# SOM_Analog_USB.net
KiCad netlist of a schematic drawn in Altium Designer
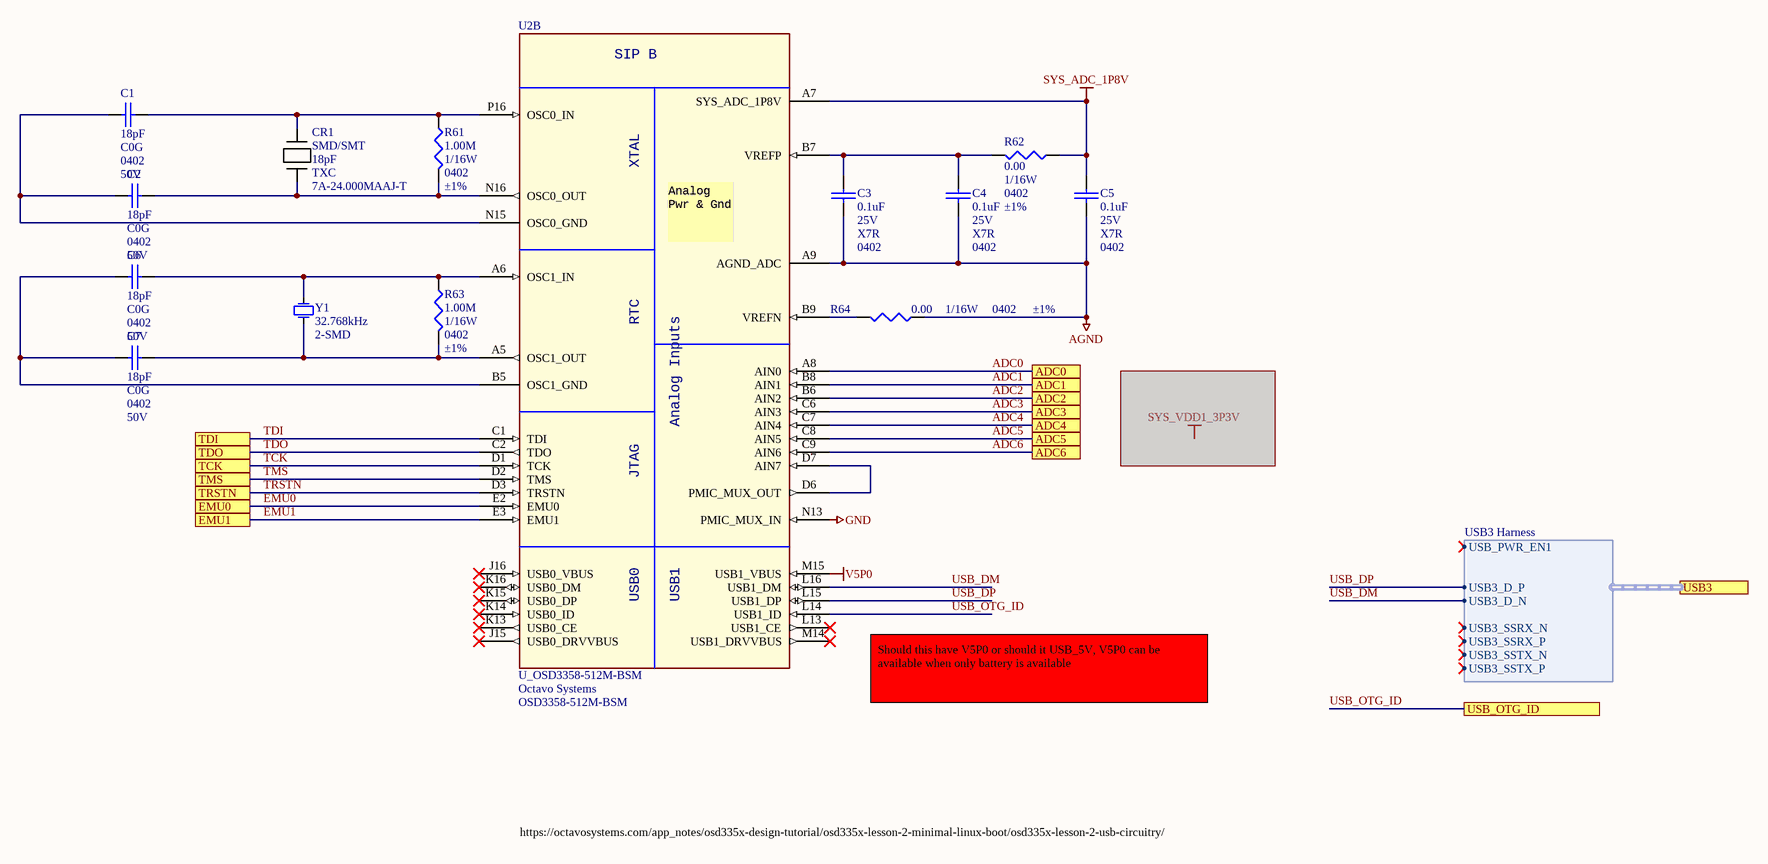
[diagram p0: SOM Analog USB.SchDoc]

(export (version "E")
  (design (tool "Eeschema 10.0.6"))
  (components
    (comp (ref "C1")
      (value "C_0402_18PF_50V")
      (footprint "C_0402")
      (fields
        (field (name "CAPACITANCE") "18pF")
        (field (name "TOLERANCE") "5%")
        (field (name "DIELECTRIC") "C0G")
        (field (name "CASE CODE (IMPERIAL)") "0402")
        (field (name "VOLTAGE RATING") "50V")
      )
      (libsource (lib "Cospan Design") (part "C_0402_18PF_50V"))
    )
    (comp (ref "C2")
      (value "C_0402_18PF_50V")
      (footprint "C_0402")
      (fields
        (field (name "CAPACITANCE") "18pF")
        (field (name "TOLERANCE") "5%")
        (field (name "DIELECTRIC") "C0G")
        (field (name "CASE CODE (IMPERIAL)") "0402")
        (field (name "VOLTAGE RATING") "50V")
      )
      (libsource (lib "Cospan Design") (part "C_0402_18PF_50V"))
    )
    (comp (ref "C3")
      (value "C_0402_0.1UF_25V")
      (footprint "C_0402")
      (description "CAP CER 0.1UF 25V X6S 0402")
      (fields
        (field (name "TOLERANCE") "10%")
        (field (name "CAPACITANCE") "0.1uF")
        (field (name "VOLTAGE - RATED") "25V")
        (field (name "TEMPERATURE COEFFICIENT") "X7R")
        (field (name "PACKAGE / CASE") "0402")
      )
      (libsource (lib "Cospan Design") (part "C_0402_0.1UF_25V"))
    )
    (comp (ref "C4")
      (value "C_0402_0.1UF_25V")
      (footprint "C_0402")
      (description "CAP CER 0.1UF 25V X6S 0402")
      (fields
        (field (name "TOLERANCE") "10%")
        (field (name "CAPACITANCE") "0.1uF")
        (field (name "VOLTAGE - RATED") "25V")
        (field (name "TEMPERATURE COEFFICIENT") "X7R")
        (field (name "PACKAGE / CASE") "0402")
      )
      (libsource (lib "Cospan Design") (part "C_0402_0.1UF_25V"))
    )
    (comp (ref "C5")
      (value "C_0402_0.1UF_25V")
      (footprint "C_0402")
      (description "CAP CER 0.1UF 25V X6S 0402")
      (fields
        (field (name "TOLERANCE") "10%")
        (field (name "CAPACITANCE") "0.1uF")
        (field (name "VOLTAGE - RATED") "25V")
        (field (name "TEMPERATURE COEFFICIENT") "X7R")
        (field (name "PACKAGE / CASE") "0402")
      )
      (libsource (lib "Cospan Design") (part "C_0402_0.1UF_25V"))
    )
    (comp (ref "C6")
      (value "C_0402_18PF_50V")
      (footprint "C_0402")
      (fields
        (field (name "CAPACITANCE") "18pF")
        (field (name "TOLERANCE") "5%")
        (field (name "DIELECTRIC") "C0G")
        (field (name "CASE CODE (IMPERIAL)") "0402")
        (field (name "VOLTAGE RATING") "50V")
      )
      (libsource (lib "Cospan Design") (part "C_0402_18PF_50V"))
    )
    (comp (ref "C7")
      (value "C_0402_18PF_50V")
      (footprint "C_0402")
      (fields
        (field (name "CAPACITANCE") "18pF")
        (field (name "TOLERANCE") "5%")
        (field (name "DIELECTRIC") "C0G")
        (field (name "CASE CODE (IMPERIAL)") "0402")
        (field (name "VOLTAGE RATING") "50V")
      )
      (libsource (lib "Cospan Design") (part "C_0402_18PF_50V"))
    )
    (comp (ref "CR1")
      (value "Y_7A-24.000MAAJ-T")
      (footprint "CRYSTAL_TXC_7A")
      (description "Imported")
      (fields
        (field (name "MANUFACTURER_PART_NUMBER") "7A-24.000MAAJ-T")
        (field (name "TOLERANCE") "30ppm")
        (field (name "CASE/PACKAGE") "SMD/SMT")
        (field (name "LOAD CAPACITANCE") "18pF")
        (field (name "MANUFACTURER 1") "TXC")
        (field (name "MANUFACTURER PART NUMBER 1") "7A-24.000MAAJ-T")
      )
      (libsource (lib "Cospan Design") (part "Y_7A-24.000MAAJ-T"))
    )
    (comp (ref "R61")
      (value "1.0M Ohms")
      (footprint "R_0402")
      (description "RES 1.00M OHM 1/16W 1% 0402 SMD")
      (fields
        (field (name "MANUFACTURER") "Vishay/Dale")
        (field (name "MANUFACTURER PART NUMBER") "CRCW04021M00FKED")
        (field (name "RESISTANCE IN OHMS") "1.00M")
        (field (name "POWER (WATTS)") "1/16W")
        (field (name "CASE") "0402")
        (field (name "TOLERANCE") "±1%")
      )
      (libsource (lib "Main Library") (part "R_0402_1.0M"))
    )
    (comp (ref "R62")
      (value "0.0 Ohms")
      (footprint "R_0402")
      (description "RES 0.00 OHM 1/16W 1% 0402 SMD")
      (fields
        (field (name "MANUFACTURER") "Yageo")
        (field (name "MANUFACTURER PART NUMBER") "RC0402JR-070RL")
        (field (name "RESISTANCE IN OHMS") "0.00")
        (field (name "POWER (WATTS)") "1/16W")
        (field (name "CASE") "0402")
        (field (name "TOLERANCE") "±1%")
      )
      (libsource (lib "Cospan Design") (part "R_0402_0.00"))
    )
    (comp (ref "R63")
      (value "1.0M Ohms")
      (footprint "R_0402")
      (description "RES 1.00M OHM 1/16W 1% 0402 SMD")
      (fields
        (field (name "MANUFACTURER") "Vishay/Dale")
        (field (name "MANUFACTURER PART NUMBER") "CRCW04021M00FKED")
        (field (name "RESISTANCE IN OHMS") "1.00M")
        (field (name "POWER (WATTS)") "1/16W")
        (field (name "CASE") "0402")
        (field (name "TOLERANCE") "±1%")
      )
      (libsource (lib "Main Library") (part "R_0402_1.0M"))
    )
    (comp (ref "R64")
      (value "0.0 Ohms")
      (footprint "R_0402")
      (description "RES 0.00 OHM 1/16W 1% 0402 SMD")
      (fields
        (field (name "MANUFACTURER") "Yageo")
        (field (name "MANUFACTURER PART NUMBER") "RC0402JR-070RL")
        (field (name "RESISTANCE IN OHMS") "0.00")
        (field (name "POWER (WATTS)") "1/16W")
        (field (name "CASE") "0402")
        (field (name "TOLERANCE") "±1%")
      )
      (libsource (lib "Cospan Design") (part "R_0402_0.00"))
    )
    (comp (ref "U2")
      (value "U_OSD3358-512M-BSM")
      (footprint "OSD335X-BGA-256")
      (fields
        (field (name "MANUFACTURER 1") "Octavo Systems")
        (field (name "MANUFACTURER PART NUMBER 1") "OSD3358-512M-BSM")
      )
      (libsource (lib "Cospan Design") (part "U_OSD3358-512M-BSM"))
    )
    (comp (ref "Y1")
      (value "32.768kHz (Tuning Fork)")
      (footprint "FC-135_CRYSTAL")
      (description "CRYSTAL 32.7680KHZ 12.5PF SMD")
      (fields
        (field (name "MANUFACTURER") "Epson Toyocom Corporation")
        (field (name "MANUFACTURER PART NUMBER") "FC-135 32.7680KA-A3")
        (field (name "FREQUENCY") "32.768kHz")
        (field (name "PACKAGE / CASE") "2-SMD")
      )
      (libsource (lib "Main Library") (part "Y_SMD_32KHZ"))
    )
  )
  (nets
    (net (code "3") (name "/ADC0") (class "Default")
      (node (ref "U2") (pin "A8") (pinfunction "AIN0_A8") (pintype "input"))
    )
    (net (code "4") (name "/ADC1") (class "Default")
      (node (ref "U2") (pin "B8") (pinfunction "AIN1_B8") (pintype "input"))
    )
    (net (code "5") (name "/ADC2") (class "Default")
      (node (ref "U2") (pin "B6") (pinfunction "AIN2_B6") (pintype "input"))
    )
    (net (code "6") (name "/ADC3") (class "Default")
      (node (ref "U2") (pin "C6") (pinfunction "AIN3_C6") (pintype "input"))
    )
    (net (code "7") (name "/ADC4") (class "Default")
      (node (ref "U2") (pin "C7") (pinfunction "AIN4_C7") (pintype "input"))
    )
    (net (code "8") (name "/ADC5") (class "Default")
      (node (ref "U2") (pin "C8") (pinfunction "AIN5_C8") (pintype "input"))
    )
    (net (code "9") (name "/ADC6") (class "Default")
      (node (ref "U2") (pin "C9") (pinfunction "AIN6_C9") (pintype "input"))
    )
    (net (code "10") (name "/EMU0") (class "Default")
      (node (ref "U2") (pin "E2") (pinfunction "EMU0_E2") (pintype "input"))
    )
    (net (code "11") (name "/EMU1") (class "Default")
      (node (ref "U2") (pin "E3") (pinfunction "EMU1_E3") (pintype "input"))
    )
    (net (code "12") (name "/TCK") (class "Default")
      (node (ref "U2") (pin "D1") (pinfunction "TCK_D1") (pintype "input"))
    )
    (net (code "13") (name "/TDI") (class "Default")
      (node (ref "U2") (pin "C1") (pinfunction "TDI_C1") (pintype "input"))
    )
    (net (code "14") (name "/TDO") (class "Default")
      (node (ref "U2") (pin "C2") (pinfunction "TDO_C2") (pintype "output"))
    )
    (net (code "15") (name "/TMS") (class "Default")
      (node (ref "U2") (pin "D2") (pinfunction "TMS_D2") (pintype "input"))
    )
    (net (code "16") (name "/TRSTN") (class "Default")
      (node (ref "U2") (pin "D3") (pinfunction "TRSTN_D3") (pintype "input"))
    )
    (net (code "17") (name "/USB_DM") (class "Default")
      (node (ref "U2") (pin "L16") (pinfunction "USB1_DM_L16") (pintype "bidirectional"))
    )
    (net (code "18") (name "/USB_DP") (class "Default")
      (node (ref "U2") (pin "L15") (pinfunction "USB1_DP_L15") (pintype "bidirectional"))
    )
    (net (code "19") (name "/USB_OTG_ID") (class "Default")
      (node (ref "U2") (pin "L14") (pinfunction "USB1_ID_L14") (pintype "input"))
    )
    (net (code "21") (name "AGND") (class "Default")
      (node (ref "C3") (pin "1") (pinfunction "1_1") (pintype "passive"))
      (node (ref "C4") (pin "1") (pinfunction "1_1") (pintype "passive"))
      (node (ref "C5") (pin "1") (pinfunction "1_1") (pintype "passive"))
      (node (ref "R64") (pin "2") (pinfunction "2_2") (pintype "passive"))
      (node (ref "U2") (pin "A9") (pinfunction "AGND_ADC_A9") (pintype "power_in"))
    )
    (net (code "22") (name "GND") (class "Default")
      (node (ref "U2") (pin "N13") (pinfunction "PMIC_MUX_IN_N13") (pintype "input"))
    )
    (net (code "23") (name "Net-(U2B-AIN7)") (class "Default")
      (node (ref "U2") (pin "D6") (pinfunction "PMIC_MUX_OUT_D6") (pintype "output"))
      (node (ref "U2") (pin "D7") (pinfunction "AIN7_D7") (pintype "input"))
    )
    (net (code "24") (name "Net-(U2B-OSC0_GND)") (class "Default")
      (node (ref "C1") (pin "1") (pinfunction "1_1") (pintype "passive"))
      (node (ref "C2") (pin "1") (pinfunction "1_1") (pintype "passive"))
      (node (ref "U2") (pin "N15") (pinfunction "OSC0_GND_N15") (pintype "power_in"))
    )
    (net (code "25") (name "Net-(U2B-OSC0_IN)") (class "Default")
      (node (ref "C1") (pin "2") (pinfunction "2_2") (pintype "passive"))
      (node (ref "CR1") (pin "2") (pinfunction "2_2") (pintype "passive"))
      (node (ref "R61") (pin "2") (pinfunction "2_2") (pintype "passive"))
      (node (ref "U2") (pin "P16") (pinfunction "OSC0_IN_P16") (pintype "input"))
    )
    (net (code "26") (name "Net-(U2B-OSC0_OUT)") (class "Default")
      (node (ref "C2") (pin "2") (pinfunction "2_2") (pintype "passive"))
      (node (ref "CR1") (pin "1") (pinfunction "1_1") (pintype "passive"))
      (node (ref "R61") (pin "1") (pinfunction "1_1") (pintype "passive"))
      (node (ref "U2") (pin "N16") (pinfunction "OSC0_OUT_N16") (pintype "output"))
    )
    (net (code "27") (name "Net-(U2B-OSC1_GND)") (class "Default")
      (node (ref "C6") (pin "1") (pinfunction "1_1") (pintype "passive"))
      (node (ref "C7") (pin "1") (pinfunction "1_1") (pintype "passive"))
      (node (ref "U2") (pin "B5") (pinfunction "OSC1_GND_B5") (pintype "power_in"))
    )
    (net (code "28") (name "Net-(U2B-OSC1_IN)") (class "Default")
      (node (ref "C6") (pin "2") (pinfunction "2_2") (pintype "passive"))
      (node (ref "R63") (pin "2") (pinfunction "2_2") (pintype "passive"))
      (node (ref "U2") (pin "A6") (pinfunction "OSC1_IN_A6") (pintype "input"))
      (node (ref "Y1") (pin "1") (pinfunction "1_1") (pintype "passive"))
    )
    (net (code "29") (name "Net-(U2B-OSC1_OUT)") (class "Default")
      (node (ref "C7") (pin "2") (pinfunction "2_2") (pintype "passive"))
      (node (ref "R63") (pin "1") (pinfunction "1_1") (pintype "passive"))
      (node (ref "U2") (pin "A5") (pinfunction "OSC1_OUT_A5") (pintype "output"))
      (node (ref "Y1") (pin "2") (pinfunction "2_2") (pintype "passive"))
    )
    (net (code "30") (name "Net-(U2B-VREFN)") (class "Default")
      (node (ref "R64") (pin "1") (pinfunction "1_1") (pintype "passive"))
      (node (ref "U2") (pin "B9") (pinfunction "VREFN_B9") (pintype "input"))
    )
    (net (code "31") (name "Net-(U2B-VREFP)") (class "Default")
      (node (ref "C3") (pin "2") (pinfunction "2_2") (pintype "passive"))
      (node (ref "C4") (pin "2") (pinfunction "2_2") (pintype "passive"))
      (node (ref "R62") (pin "1") (pinfunction "1_1") (pintype "passive"))
      (node (ref "U2") (pin "B7") (pinfunction "VREFP_B7") (pintype "input"))
    )
    (net (code "32") (name "SYS_ADC_1P8V") (class "Default")
      (node (ref "C5") (pin "2") (pinfunction "2_2") (pintype "passive"))
      (node (ref "R62") (pin "2") (pinfunction "2_2") (pintype "passive"))
      (node (ref "U2") (pin "A7") (pinfunction "SYS_ADC_1P8V_A7") (pintype "power_in"))
    )
    (net (code "34") (name "V5P0") (class "Default")
      (node (ref "U2") (pin "M15") (pinfunction "USB1_VBUS_M15") (pintype "input"))
    )
    (net (code "35") (name "unconnected-(U2B-USB0_CE-PadK13)") (class "Default")
      (node (ref "U2") (pin "K13") (pinfunction "USB0_CE_K13") (pintype "output+no_connect"))
    )
    (net (code "36") (name "unconnected-(U2B-USB0_DM-PadK16)") (class "Default")
      (node (ref "U2") (pin "K16") (pinfunction "USB0_DM_K16") (pintype "bidirectional+no_connect"))
    )
    (net (code "37") (name "unconnected-(U2B-USB0_DP-PadK15)") (class "Default")
      (node (ref "U2") (pin "K15") (pinfunction "USB0_DP_K15") (pintype "bidirectional+no_connect"))
    )
    (net (code "38") (name "unconnected-(U2B-USB0_DRVVBUS-PadJ15)") (class "Default")
      (node (ref "U2") (pin "J15") (pinfunction "USB0_DRVVBUS_J15") (pintype "output+no_connect"))
    )
    (net (code "39") (name "unconnected-(U2B-USB0_ID-PadK14)") (class "Default")
      (node (ref "U2") (pin "K14") (pinfunction "USB0_ID_K14") (pintype "input+no_connect"))
    )
    (net (code "40") (name "unconnected-(U2B-USB0_VBUS-PadJ16)") (class "Default")
      (node (ref "U2") (pin "J16") (pinfunction "USB0_VBUS_J16") (pintype "input+no_connect"))
    )
    (net (code "41") (name "unconnected-(U2B-USB1_CE-PadL13)") (class "Default")
      (node (ref "U2") (pin "L13") (pinfunction "USB1_CE_L13") (pintype "output+no_connect"))
    )
    (net (code "42") (name "unconnected-(U2B-USB1_DRVVBUS-PadM14)") (class "Default")
      (node (ref "U2") (pin "M14") (pinfunction "USB1_DRVVBUS_M14") (pintype "output+no_connect"))
    )
  )
)
